# rcstick-f-small.net
KiCad netlist of a schematic drawn in EAGLE
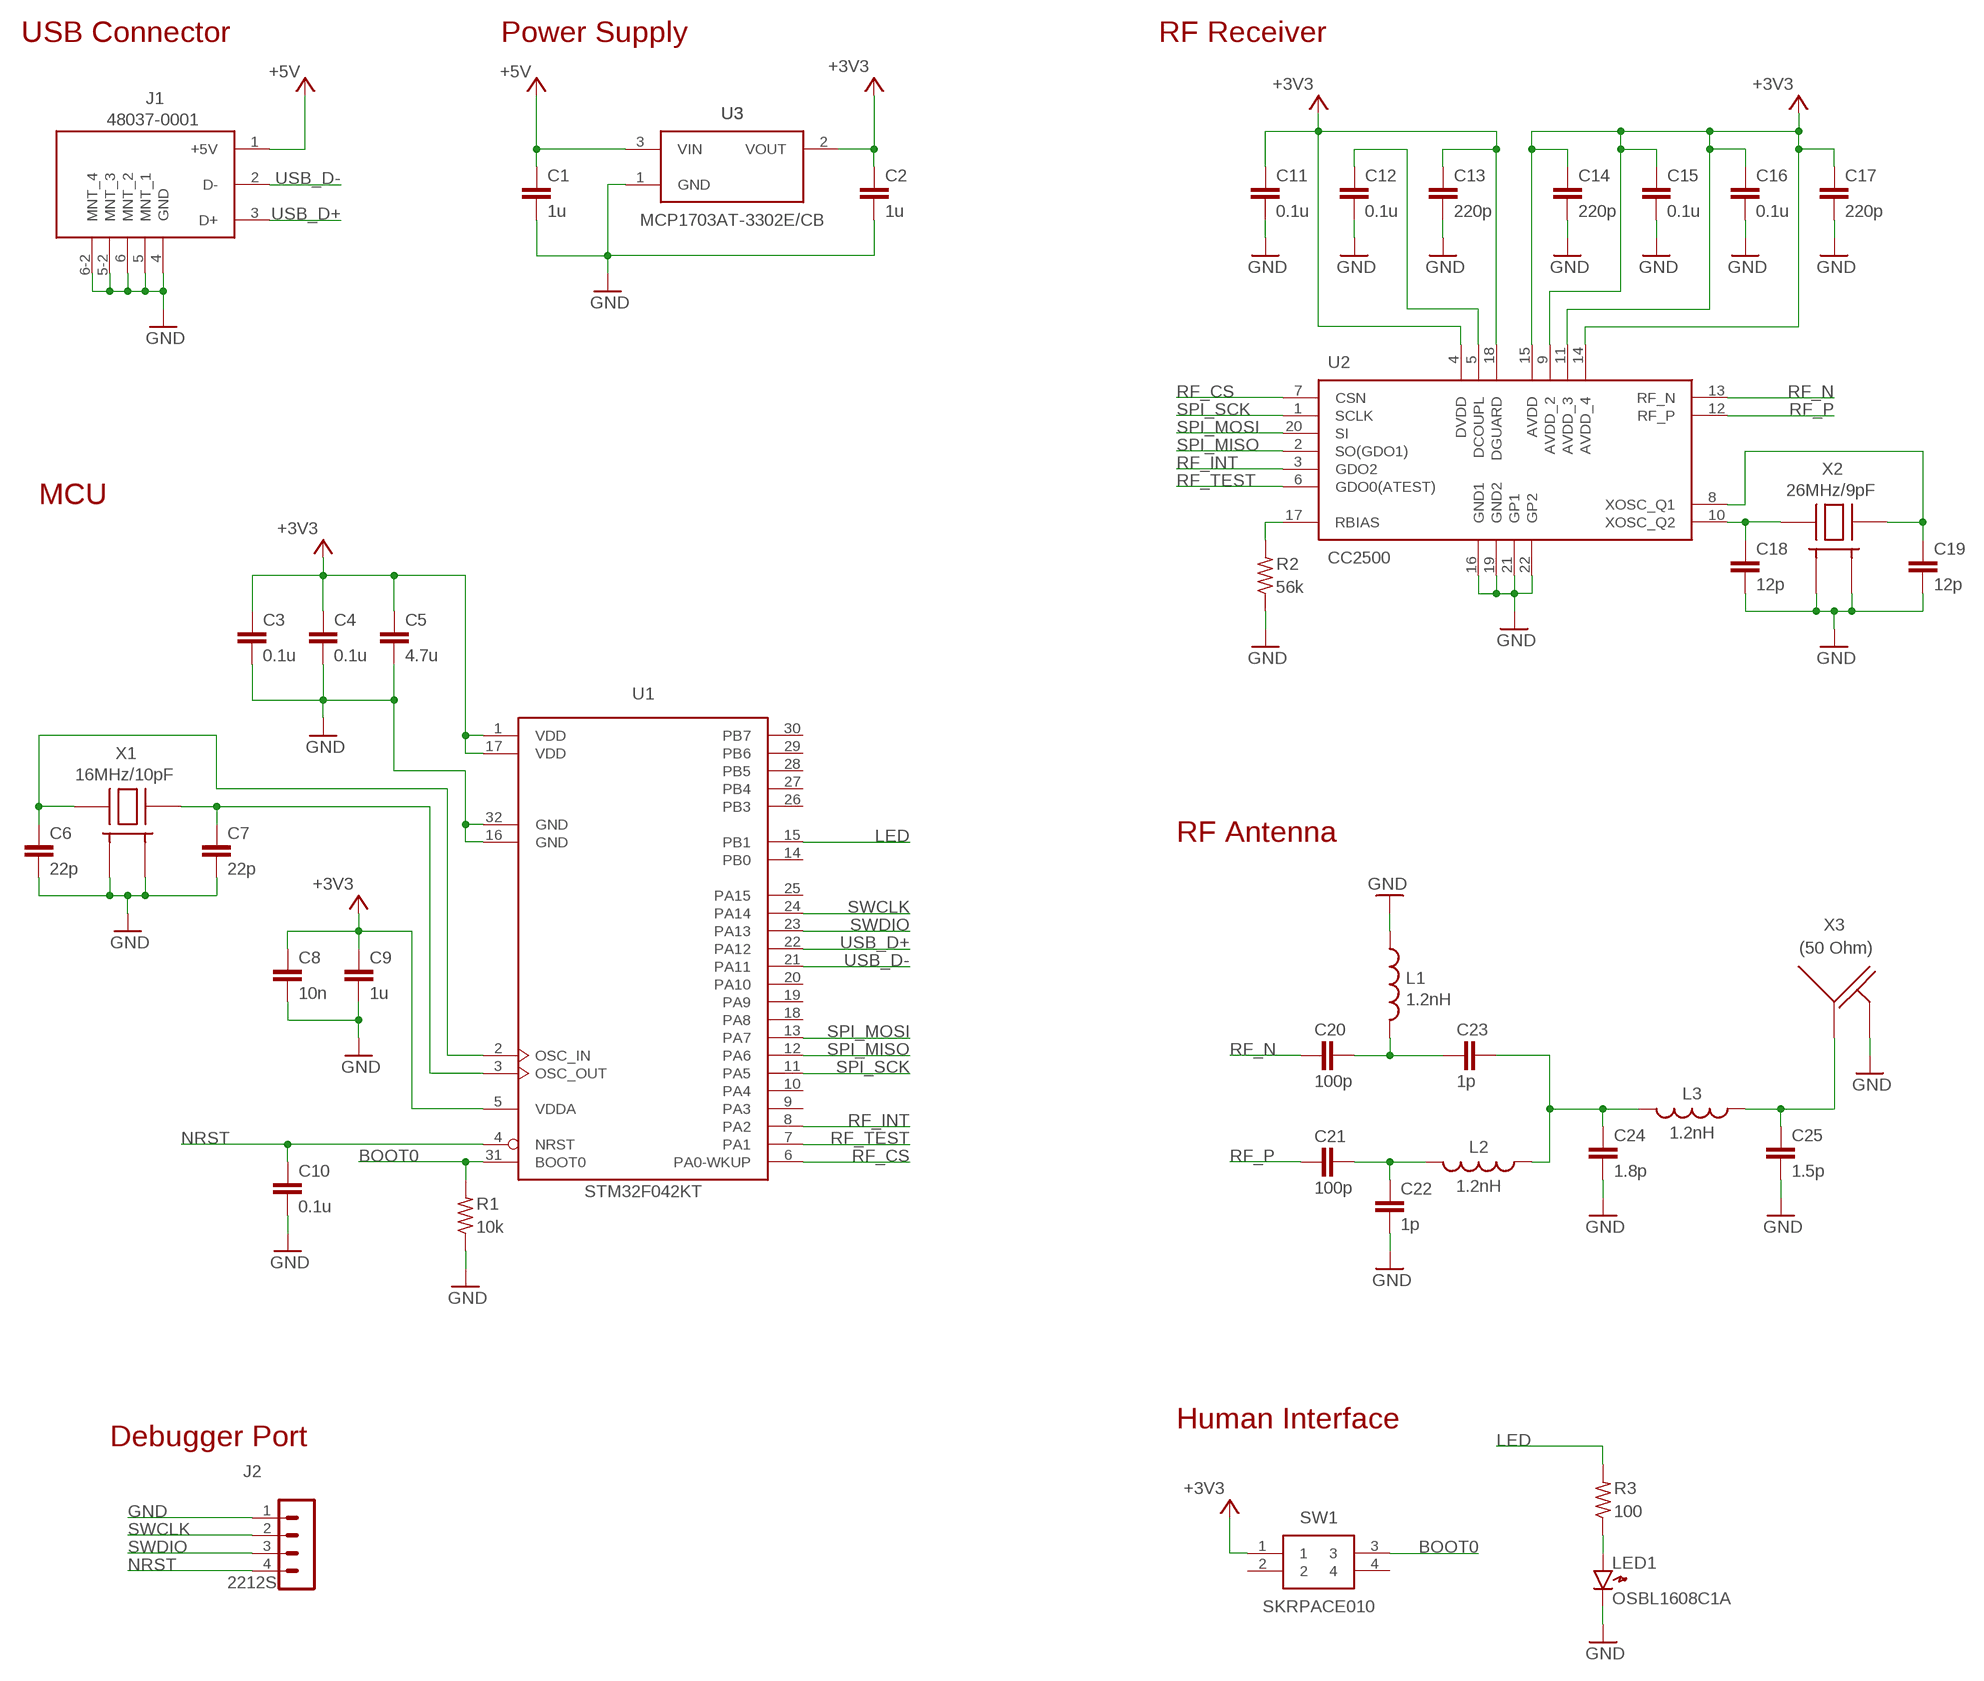
[diagram p0: schematic, sheet 1]

(export (version "E")
  (design (tool "Eeschema 10.0.6"))
  (components
    (comp (ref "C1")
      (value "1u")
      (footprint "eagle-import:RCL_C0402_HS")
      (libsource (lib "eagle-import") (part "RCL_C-EUC0402-HS"))
    )
    (comp (ref "C2")
      (value "1u")
      (footprint "eagle-import:RCL_C0402_HS")
      (libsource (lib "eagle-import") (part "RCL_C-EUC0402-HS"))
    )
    (comp (ref "C3")
      (value "0.1u")
      (footprint "eagle-import:RCL_C0402_HS")
      (libsource (lib "eagle-import") (part "RCL_C-EUC0402-HS"))
    )
    (comp (ref "C4")
      (value "0.1u")
      (footprint "eagle-import:RCL_C0402_HS")
      (libsource (lib "eagle-import") (part "RCL_C-EUC0402-HS"))
    )
    (comp (ref "C5")
      (value "4.7u")
      (footprint "eagle-import:RCL_C0402_HS")
      (libsource (lib "eagle-import") (part "RCL_C-EUC0402-HS"))
    )
    (comp (ref "C6")
      (value "22p")
      (footprint "eagle-import:RCL_C0402_HS")
      (libsource (lib "eagle-import") (part "RCL_C-EUC0402-HS"))
    )
    (comp (ref "C7")
      (value "22p")
      (footprint "eagle-import:RCL_C0402_HS")
      (libsource (lib "eagle-import") (part "RCL_C-EUC0402-HS"))
    )
    (comp (ref "C8")
      (value "10n")
      (footprint "eagle-import:RCL_C0402_HS")
      (libsource (lib "eagle-import") (part "RCL_C-EUC0402-HS"))
    )
    (comp (ref "C9")
      (value "1u")
      (footprint "eagle-import:RCL_C0402_HS")
      (libsource (lib "eagle-import") (part "RCL_C-EUC0402-HS"))
    )
    (comp (ref "C10")
      (value "0.1u")
      (footprint "eagle-import:RCL_C0402_HS")
      (libsource (lib "eagle-import") (part "RCL_C-EUC0402-HS"))
    )
    (comp (ref "C11")
      (value "0.1u")
      (footprint "eagle-import:RCL_C0402_HS")
      (libsource (lib "eagle-import") (part "RCL_C-EUC0402-HS"))
    )
    (comp (ref "C12")
      (value "0.1u")
      (footprint "eagle-import:RCL_C0402_HS")
      (libsource (lib "eagle-import") (part "RCL_C-EUC0402-HS"))
    )
    (comp (ref "C13")
      (value "220p")
      (footprint "eagle-import:RCL_C0402_HS")
      (libsource (lib "eagle-import") (part "RCL_C-EUC0402-HS"))
    )
    (comp (ref "C14")
      (value "220p")
      (footprint "eagle-import:RCL_C0402_HS")
      (libsource (lib "eagle-import") (part "RCL_C-EUC0402-HS"))
    )
    (comp (ref "C15")
      (value "0.1u")
      (footprint "eagle-import:RCL_C0402_HS")
      (libsource (lib "eagle-import") (part "RCL_C-EUC0402-HS"))
    )
    (comp (ref "C16")
      (value "0.1u")
      (footprint "eagle-import:RCL_C0402_HS")
      (libsource (lib "eagle-import") (part "RCL_C-EUC0402-HS"))
    )
    (comp (ref "C17")
      (value "220p")
      (footprint "eagle-import:RCL_C0402_HS")
      (libsource (lib "eagle-import") (part "RCL_C-EUC0402-HS"))
    )
    (comp (ref "C18")
      (value "12p")
      (footprint "eagle-import:RCL_C0402_HS")
      (libsource (lib "eagle-import") (part "RCL_C-EUC0402-HS"))
    )
    (comp (ref "C19")
      (value "12p")
      (footprint "eagle-import:RCL_C0402_HS")
      (libsource (lib "eagle-import") (part "RCL_C-EUC0402-HS"))
    )
    (comp (ref "C20")
      (value "100p")
      (footprint "eagle-import:RCL_C0402_HS")
      (libsource (lib "eagle-import") (part "RCL_C-EUC0402-HS"))
    )
    (comp (ref "C21")
      (value "100p")
      (footprint "eagle-import:RCL_C0402_HS")
      (libsource (lib "eagle-import") (part "RCL_C-EUC0402-HS"))
    )
    (comp (ref "C22")
      (value "1p")
      (footprint "eagle-import:RCL_C0402_HS")
      (libsource (lib "eagle-import") (part "RCL_C-EUC0402-HS"))
    )
    (comp (ref "C23")
      (value "1p")
      (footprint "eagle-import:RCL_C0402_HS")
      (libsource (lib "eagle-import") (part "RCL_C-EUC0402-HS"))
    )
    (comp (ref "C24")
      (value "1.8p")
      (footprint "eagle-import:RCL_C0402_HS")
      (libsource (lib "eagle-import") (part "RCL_C-EUC0402-HS"))
    )
    (comp (ref "C25")
      (value "1.5p")
      (footprint "eagle-import:RCL_C0402_HS")
      (libsource (lib "eagle-import") (part "RCL_C-EUC0402-HS"))
    )
    (comp (ref "J1")
      (value "MOLEX_48037-0001")
      (footprint "eagle-import:MOLEX_48037-0001_1")
      (libsource (lib "eagle-import") (part "MOLEX_48037-0001"))
    )
    (comp (ref "J2")
      (value "2212S")
      (footprint "eagle-import:53047-0410")
      (libsource (lib "eagle-import") (part "53047-0410"))
    )
    (comp (ref "L1")
      (value "1.2nH")
      (footprint "eagle-import:RCL_L0402_HS")
      (libsource (lib "eagle-import") (part "RCL_L-USL0402-HS"))
    )
    (comp (ref "L2")
      (value "1.2nH")
      (footprint "eagle-import:RCL_L0402_HS")
      (libsource (lib "eagle-import") (part "RCL_L-USL0402-HS"))
    )
    (comp (ref "L3")
      (value "1.2nH")
      (footprint "eagle-import:RCL_L0402_HS")
      (libsource (lib "eagle-import") (part "RCL_L-USL0402-HS"))
    )
    (comp (ref "LED1")
      (value "OSBL1608C1A")
      (footprint "eagle-import:LED1608")
      (libsource (lib "eagle-import") (part "LED1608"))
    )
    (comp (ref "R1")
      (value "10k")
      (footprint "eagle-import:RCL_R0402_HS")
      (libsource (lib "eagle-import") (part "RCL_R-US_R0402-HS"))
    )
    (comp (ref "R2")
      (value "56k")
      (footprint "eagle-import:RCL_R0402_HS")
      (libsource (lib "eagle-import") (part "RCL_R-US_R0402-HS"))
    )
    (comp (ref "R3")
      (value "100")
      (footprint "eagle-import:RCL_R0402_HS")
      (libsource (lib "eagle-import") (part "RCL_R-US_R0402-HS"))
    )
    (comp (ref "SW1")
      (value "SKRPACE010")
      (footprint "eagle-import:SMT(4.2X3.2)")
      (libsource (lib "eagle-import") (part "SKRPACE010"))
    )
    (comp (ref "U1")
      (value "STM32F042KT")
      (footprint "eagle-import:LQFP32-M")
      (libsource (lib "eagle-import") (part "STM32F042KT"))
    )
    (comp (ref "U2")
      (value "CC2500")
      (footprint "eagle-import:CC2500-RTY1_CC2500-HS")
      (libsource (lib "eagle-import") (part "CC2500-HS"))
    )
    (comp (ref "U3")
      (value "MCP1703AT-3302E/CB")
      (footprint "eagle-import:SOT23")
      (libsource (lib "eagle-import") (part "LDO-REGULATOR"))
    )
    (comp (ref "X1")
      (value "16MHz/10pF")
      (footprint "eagle-import:CRYSTAL3225-HS")
      (libsource (lib "eagle-import") (part "CRYSTAL3225HS"))
    )
    (comp (ref "X2")
      (value "26MHz/9pF")
      (footprint "eagle-import:CRYSTAL3225-HS")
      (libsource (lib "eagle-import") (part "CRYSTAL3225HS"))
    )
    (comp (ref "X3")
      (value "(50 Ohm)")
      (footprint "eagle-import:2.4GHZ-INVERTED-F-SMALL-FLIP")
      (libsource (lib "eagle-import") (part "2.4GHZ-INVERED-FSMALL-FLIP"))
    )
  )
  (nets
    (net (code "1") (name "+3V3") (class "Default")
      (node (ref "C11") (pin "1") (pinfunction "1_1") (pintype "passive"))
      (node (ref "C13") (pin "1") (pinfunction "1_1") (pintype "passive"))
      (node (ref "C14") (pin "1") (pinfunction "1_1") (pintype "passive"))
      (node (ref "C15") (pin "1") (pinfunction "1_1") (pintype "passive"))
      (node (ref "C16") (pin "1") (pinfunction "1_1") (pintype "passive"))
      (node (ref "C17") (pin "1") (pinfunction "1_1") (pintype "passive"))
      (node (ref "C2") (pin "1") (pinfunction "1_1") (pintype "passive"))
      (node (ref "C3") (pin "1") (pinfunction "1_1") (pintype "passive"))
      (node (ref "C4") (pin "1") (pinfunction "1_1") (pintype "passive"))
      (node (ref "C5") (pin "1") (pinfunction "1_1") (pintype "passive"))
      (node (ref "C8") (pin "1") (pinfunction "1_1") (pintype "passive"))
      (node (ref "C9") (pin "1") (pinfunction "1_1") (pintype "passive"))
      (node (ref "SW1") (pin "1") (pinfunction "1_1") (pintype "bidirectional"))
      (node (ref "U1") (pin "1") (pinfunction "VDD_1") (pintype "power_in"))
      (node (ref "U1") (pin "17") (pinfunction "VDD_17") (pintype "power_in"))
      (node (ref "U1") (pin "5") (pinfunction "VDDA_5") (pintype "power_in"))
      (node (ref "U2") (pin "11") (pinfunction "AVDD_3_11") (pintype "bidirectional"))
      (node (ref "U2") (pin "14") (pinfunction "AVDD_4_14") (pintype "bidirectional"))
      (node (ref "U2") (pin "15") (pinfunction "AVDD_15") (pintype "bidirectional"))
      (node (ref "U2") (pin "18") (pinfunction "DGUARD_18") (pintype "bidirectional"))
      (node (ref "U2") (pin "4") (pinfunction "DVDD_4") (pintype "bidirectional"))
      (node (ref "U2") (pin "9") (pinfunction "AVDD_2_9") (pintype "bidirectional"))
      (node (ref "U3") (pin "2") (pinfunction "VOUT_2") (pintype "bidirectional"))
    )
    (net (code "2") (name "+5V") (class "Default")
      (node (ref "C1") (pin "1") (pinfunction "1_1") (pintype "passive"))
      (node (ref "J1") (pin "1") (pinfunction "+5V_1") (pintype "bidirectional"))
      (node (ref "U3") (pin "3") (pinfunction "VIN_3") (pintype "bidirectional"))
    )
    (net (code "3") (name "/BOOT0") (class "Default")
      (node (ref "R1") (pin "2") (pinfunction "2_2") (pintype "passive"))
      (node (ref "SW1") (pin "3") (pinfunction "3_3") (pintype "bidirectional"))
      (node (ref "U1") (pin "31") (pinfunction "BOOT0_31") (pintype "input"))
    )
    (net (code "4") (name "/LED") (class "Default")
      (node (ref "R3") (pin "2") (pinfunction "2_2") (pintype "passive"))
      (node (ref "U1") (pin "15") (pinfunction "PB1_15") (pintype "bidirectional"))
    )
    (net (code "5") (name "/NRST") (class "Default")
      (node (ref "C10") (pin "1") (pinfunction "1_1") (pintype "passive"))
      (node (ref "J2") (pin "4") (pinfunction "4_4") (pintype "passive"))
      (node (ref "U1") (pin "4") (pinfunction "NRST_4") (pintype "bidirectional"))
    )
    (net (code "6") (name "/RF_CS") (class "Default")
      (node (ref "U1") (pin "6") (pinfunction "PA0-WKUP_6") (pintype "bidirectional"))
      (node (ref "U2") (pin "7") (pinfunction "CSN_7") (pintype "bidirectional"))
    )
    (net (code "7") (name "/RF_INT") (class "Default")
      (node (ref "U1") (pin "8") (pinfunction "PA2_8") (pintype "bidirectional"))
      (node (ref "U2") (pin "3") (pinfunction "GDO2_3") (pintype "bidirectional"))
    )
    (net (code "8") (name "/RF_N") (class "Default")
      (node (ref "C20") (pin "1") (pinfunction "1_1") (pintype "passive"))
      (node (ref "U2") (pin "13") (pinfunction "RF_N_13") (pintype "bidirectional"))
    )
    (net (code "9") (name "/RF_P") (class "Default")
      (node (ref "C21") (pin "1") (pinfunction "1_1") (pintype "passive"))
      (node (ref "U2") (pin "12") (pinfunction "RF_P_12") (pintype "bidirectional"))
    )
    (net (code "10") (name "/RF_TEST") (class "Default")
      (node (ref "U1") (pin "7") (pinfunction "PA1_7") (pintype "bidirectional"))
      (node (ref "U2") (pin "6") (pinfunction "GDO0(ATEST)_6") (pintype "bidirectional"))
    )
    (net (code "11") (name "/SPI_MISO") (class "Default")
      (node (ref "U1") (pin "12") (pinfunction "PA6_12") (pintype "bidirectional"))
      (node (ref "U2") (pin "2") (pinfunction "SO(GDO1)_2") (pintype "bidirectional"))
    )
    (net (code "12") (name "/SPI_MOSI") (class "Default")
      (node (ref "U1") (pin "13") (pinfunction "PA7_13") (pintype "bidirectional"))
      (node (ref "U2") (pin "20") (pinfunction "SI_20") (pintype "bidirectional"))
    )
    (net (code "13") (name "/SPI_SCK") (class "Default")
      (node (ref "U1") (pin "11") (pinfunction "PA5_11") (pintype "bidirectional"))
      (node (ref "U2") (pin "1") (pinfunction "SCLK_1") (pintype "bidirectional"))
    )
    (net (code "14") (name "/SWCLK") (class "Default")
      (node (ref "J2") (pin "2") (pinfunction "2_2") (pintype "passive"))
      (node (ref "U1") (pin "24") (pinfunction "PA14_24") (pintype "bidirectional"))
    )
    (net (code "15") (name "/SWDIO") (class "Default")
      (node (ref "J2") (pin "3") (pinfunction "3_3") (pintype "passive"))
      (node (ref "U1") (pin "23") (pinfunction "PA13_23") (pintype "bidirectional"))
    )
    (net (code "16") (name "/USB_D+") (class "Default")
      (node (ref "J1") (pin "3") (pinfunction "D+_3") (pintype "bidirectional"))
      (node (ref "U1") (pin "22") (pinfunction "PA12_22") (pintype "bidirectional"))
    )
    (net (code "17") (name "/USB_D-") (class "Default")
      (node (ref "J1") (pin "2") (pinfunction "D-_2") (pintype "bidirectional"))
      (node (ref "U1") (pin "21") (pinfunction "PA11_21") (pintype "bidirectional"))
    )
    (net (code "18") (name "GND") (class "Default")
      (node (ref "C1") (pin "2") (pinfunction "2_2") (pintype "passive"))
      (node (ref "C10") (pin "2") (pinfunction "2_2") (pintype "passive"))
      (node (ref "C11") (pin "2") (pinfunction "2_2") (pintype "passive"))
      (node (ref "C12") (pin "2") (pinfunction "2_2") (pintype "passive"))
      (node (ref "C13") (pin "2") (pinfunction "2_2") (pintype "passive"))
      (node (ref "C14") (pin "2") (pinfunction "2_2") (pintype "passive"))
      (node (ref "C15") (pin "2") (pinfunction "2_2") (pintype "passive"))
      (node (ref "C16") (pin "2") (pinfunction "2_2") (pintype "passive"))
      (node (ref "C17") (pin "2") (pinfunction "2_2") (pintype "passive"))
      (node (ref "C18") (pin "2") (pinfunction "2_2") (pintype "passive"))
      (node (ref "C19") (pin "2") (pinfunction "2_2") (pintype "passive"))
      (node (ref "C2") (pin "2") (pinfunction "2_2") (pintype "passive"))
      (node (ref "C22") (pin "2") (pinfunction "2_2") (pintype "passive"))
      (node (ref "C24") (pin "2") (pinfunction "2_2") (pintype "passive"))
      (node (ref "C25") (pin "2") (pinfunction "2_2") (pintype "passive"))
      (node (ref "C3") (pin "2") (pinfunction "2_2") (pintype "passive"))
      (node (ref "C4") (pin "2") (pinfunction "2_2") (pintype "passive"))
      (node (ref "C5") (pin "2") (pinfunction "2_2") (pintype "passive"))
      (node (ref "C6") (pin "2") (pinfunction "2_2") (pintype "passive"))
      (node (ref "C7") (pin "2") (pinfunction "2_2") (pintype "passive"))
      (node (ref "C8") (pin "2") (pinfunction "2_2") (pintype "passive"))
      (node (ref "C9") (pin "2") (pinfunction "2_2") (pintype "passive"))
      (node (ref "J1") (pin "4") (pinfunction "GND_4") (pintype "bidirectional"))
      (node (ref "J1") (pin "5") (pinfunction "MNT_1_5") (pintype "bidirectional"))
      (node (ref "J1") (pin "5-2") (pinfunction "MNT_3_5-2") (pintype "bidirectional"))
      (node (ref "J1") (pin "6") (pinfunction "MNT_2_6") (pintype "bidirectional"))
      (node (ref "J1") (pin "6-2") (pinfunction "MNT_4_6-2") (pintype "bidirectional"))
      (node (ref "J2") (pin "1") (pinfunction "1_1") (pintype "passive"))
      (node (ref "L1") (pin "1") (pinfunction "1_1") (pintype "passive"))
      (node (ref "LED1") (pin "K") (pinfunction "K_K") (pintype "passive"))
      (node (ref "R1") (pin "1") (pinfunction "1_1") (pintype "passive"))
      (node (ref "R2") (pin "1") (pinfunction "1_1") (pintype "passive"))
      (node (ref "U1") (pin "16") (pinfunction "GND_16") (pintype "power_in"))
      (node (ref "U1") (pin "32") (pinfunction "GND_32") (pintype "power_in"))
      (node (ref "U2") (pin "16") (pinfunction "GND1_16") (pintype "bidirectional"))
      (node (ref "U2") (pin "19") (pinfunction "GND2_19") (pintype "bidirectional"))
      (node (ref "U2") (pin "21") (pinfunction "GP1_21") (pintype "bidirectional"))
      (node (ref "U2") (pin "22") (pinfunction "GP2_22") (pintype "bidirectional"))
      (node (ref "U3") (pin "1") (pinfunction "GND_1") (pintype "bidirectional"))
      (node (ref "X1") (pin "2") (pinfunction "GND_1_2") (pintype "bidirectional"))
      (node (ref "X1") (pin "4") (pinfunction "GND_2_4") (pintype "bidirectional"))
      (node (ref "X2") (pin "2") (pinfunction "GND_1_2") (pintype "bidirectional"))
      (node (ref "X2") (pin "4") (pinfunction "GND_2_4") (pintype "bidirectional"))
      (node (ref "X3") (pin "2") (pinfunction "GND_2") (pintype "bidirectional"))
    )
    (net (code "19") (name "Net-(C20-Pad2)") (class "Default")
      (node (ref "C20") (pin "2") (pinfunction "2_2") (pintype "passive"))
      (node (ref "C23") (pin "1") (pinfunction "1_1") (pintype "passive"))
      (node (ref "L1") (pin "2") (pinfunction "2_2") (pintype "passive"))
    )
    (net (code "20") (name "Net-(C21-Pad2)") (class "Default")
      (node (ref "C21") (pin "2") (pinfunction "2_2") (pintype "passive"))
      (node (ref "C22") (pin "1") (pinfunction "1_1") (pintype "passive"))
      (node (ref "L2") (pin "2") (pinfunction "2_2") (pintype "passive"))
    )
    (net (code "21") (name "Net-(C23-Pad2)") (class "Default")
      (node (ref "C23") (pin "2") (pinfunction "2_2") (pintype "passive"))
      (node (ref "C24") (pin "1") (pinfunction "1_1") (pintype "passive"))
      (node (ref "L2") (pin "1") (pinfunction "1_1") (pintype "passive"))
      (node (ref "L3") (pin "2") (pinfunction "2_2") (pintype "passive"))
    )
    (net (code "22") (name "Net-(LED1-PadA)") (class "Default")
      (node (ref "LED1") (pin "A") (pinfunction "A_A") (pintype "passive"))
      (node (ref "R3") (pin "1") (pinfunction "1_1") (pintype "passive"))
    )
    (net (code "23") (name "Net-(U1-OSC_IN)") (class "Default")
      (node (ref "C6") (pin "1") (pinfunction "1_1") (pintype "passive"))
      (node (ref "U1") (pin "2") (pinfunction "OSC_IN_2") (pintype "bidirectional"))
      (node (ref "X1") (pin "1") (pinfunction "HOT_1_1") (pintype "bidirectional"))
    )
    (net (code "24") (name "Net-(U1-OSC_OUT)") (class "Default")
      (node (ref "C7") (pin "1") (pinfunction "1_1") (pintype "passive"))
      (node (ref "U1") (pin "3") (pinfunction "OSC_OUT_3") (pintype "bidirectional"))
      (node (ref "X1") (pin "3") (pinfunction "HOT_2_3") (pintype "bidirectional"))
    )
    (net (code "25") (name "Net-(U2-DCOUPL)") (class "Default")
      (node (ref "C12") (pin "1") (pinfunction "1_1") (pintype "passive"))
      (node (ref "U2") (pin "5") (pinfunction "DCOUPL_5") (pintype "bidirectional"))
    )
    (net (code "26") (name "Net-(U2-RBIAS)") (class "Default")
      (node (ref "R2") (pin "2") (pinfunction "2_2") (pintype "passive"))
      (node (ref "U2") (pin "17") (pinfunction "RBIAS_17") (pintype "bidirectional"))
    )
    (net (code "27") (name "Net-(U2-XOSC_Q1)") (class "Default")
      (node (ref "C19") (pin "1") (pinfunction "1_1") (pintype "passive"))
      (node (ref "U2") (pin "8") (pinfunction "XOSC_Q1_8") (pintype "bidirectional"))
      (node (ref "X2") (pin "3") (pinfunction "HOT_2_3") (pintype "bidirectional"))
    )
    (net (code "28") (name "Net-(U2-XOSC_Q2)") (class "Default")
      (node (ref "C18") (pin "1") (pinfunction "1_1") (pintype "passive"))
      (node (ref "U2") (pin "10") (pinfunction "XOSC_Q2_10") (pintype "bidirectional"))
      (node (ref "X2") (pin "1") (pinfunction "HOT_1_1") (pintype "bidirectional"))
    )
    (net (code "29") (name "Net-(X3-ANT)") (class "Default")
      (node (ref "C25") (pin "1") (pinfunction "1_1") (pintype "passive"))
      (node (ref "L3") (pin "1") (pinfunction "1_1") (pintype "passive"))
      (node (ref "X3") (pin "1") (pinfunction "ANT_1") (pintype "bidirectional"))
    )
    (net (code "30") (name "unconnected-(SW1-Pad2)") (class "Default")
      (node (ref "SW1") (pin "2") (pinfunction "2_2") (pintype "bidirectional"))
    )
    (net (code "31") (name "unconnected-(SW1-Pad4)") (class "Default")
      (node (ref "SW1") (pin "4") (pinfunction "4_4") (pintype "bidirectional"))
    )
    (net (code "32") (name "unconnected-(U1-PA3-Pad9)") (class "Default")
      (node (ref "U1") (pin "9") (pinfunction "PA3_9") (pintype "bidirectional"))
    )
    (net (code "33") (name "unconnected-(U1-PA4-Pad10)") (class "Default")
      (node (ref "U1") (pin "10") (pinfunction "PA4_10") (pintype "bidirectional"))
    )
    (net (code "34") (name "unconnected-(U1-PA8-Pad18)") (class "Default")
      (node (ref "U1") (pin "18") (pinfunction "PA8_18") (pintype "bidirectional"))
    )
    (net (code "35") (name "unconnected-(U1-PA9-Pad19)") (class "Default")
      (node (ref "U1") (pin "19") (pinfunction "PA9_19") (pintype "bidirectional"))
    )
    (net (code "36") (name "unconnected-(U1-PA10-Pad20)") (class "Default")
      (node (ref "U1") (pin "20") (pinfunction "PA10_20") (pintype "bidirectional"))
    )
    (net (code "37") (name "unconnected-(U1-PA15-Pad25)") (class "Default")
      (node (ref "U1") (pin "25") (pinfunction "PA15_25") (pintype "bidirectional"))
    )
    (net (code "38") (name "unconnected-(U1-PB0-Pad14)") (class "Default")
      (node (ref "U1") (pin "14") (pinfunction "PB0_14") (pintype "bidirectional"))
    )
    (net (code "39") (name "unconnected-(U1-PB3-Pad26)") (class "Default")
      (node (ref "U1") (pin "26") (pinfunction "PB3_26") (pintype "bidirectional"))
    )
    (net (code "40") (name "unconnected-(U1-PB4-Pad27)") (class "Default")
      (node (ref "U1") (pin "27") (pinfunction "PB4_27") (pintype "bidirectional"))
    )
    (net (code "41") (name "unconnected-(U1-PB5-Pad28)") (class "Default")
      (node (ref "U1") (pin "28") (pinfunction "PB5_28") (pintype "bidirectional"))
    )
    (net (code "42") (name "unconnected-(U1-PB6-Pad29)") (class "Default")
      (node (ref "U1") (pin "29") (pinfunction "PB6_29") (pintype "bidirectional"))
    )
    (net (code "43") (name "unconnected-(U1-PB7-Pad30)") (class "Default")
      (node (ref "U1") (pin "30") (pinfunction "PB7_30") (pintype "bidirectional"))
    )
  )
)
